# Input.net
KiCad netlist of a schematic drawn in Altium Designer
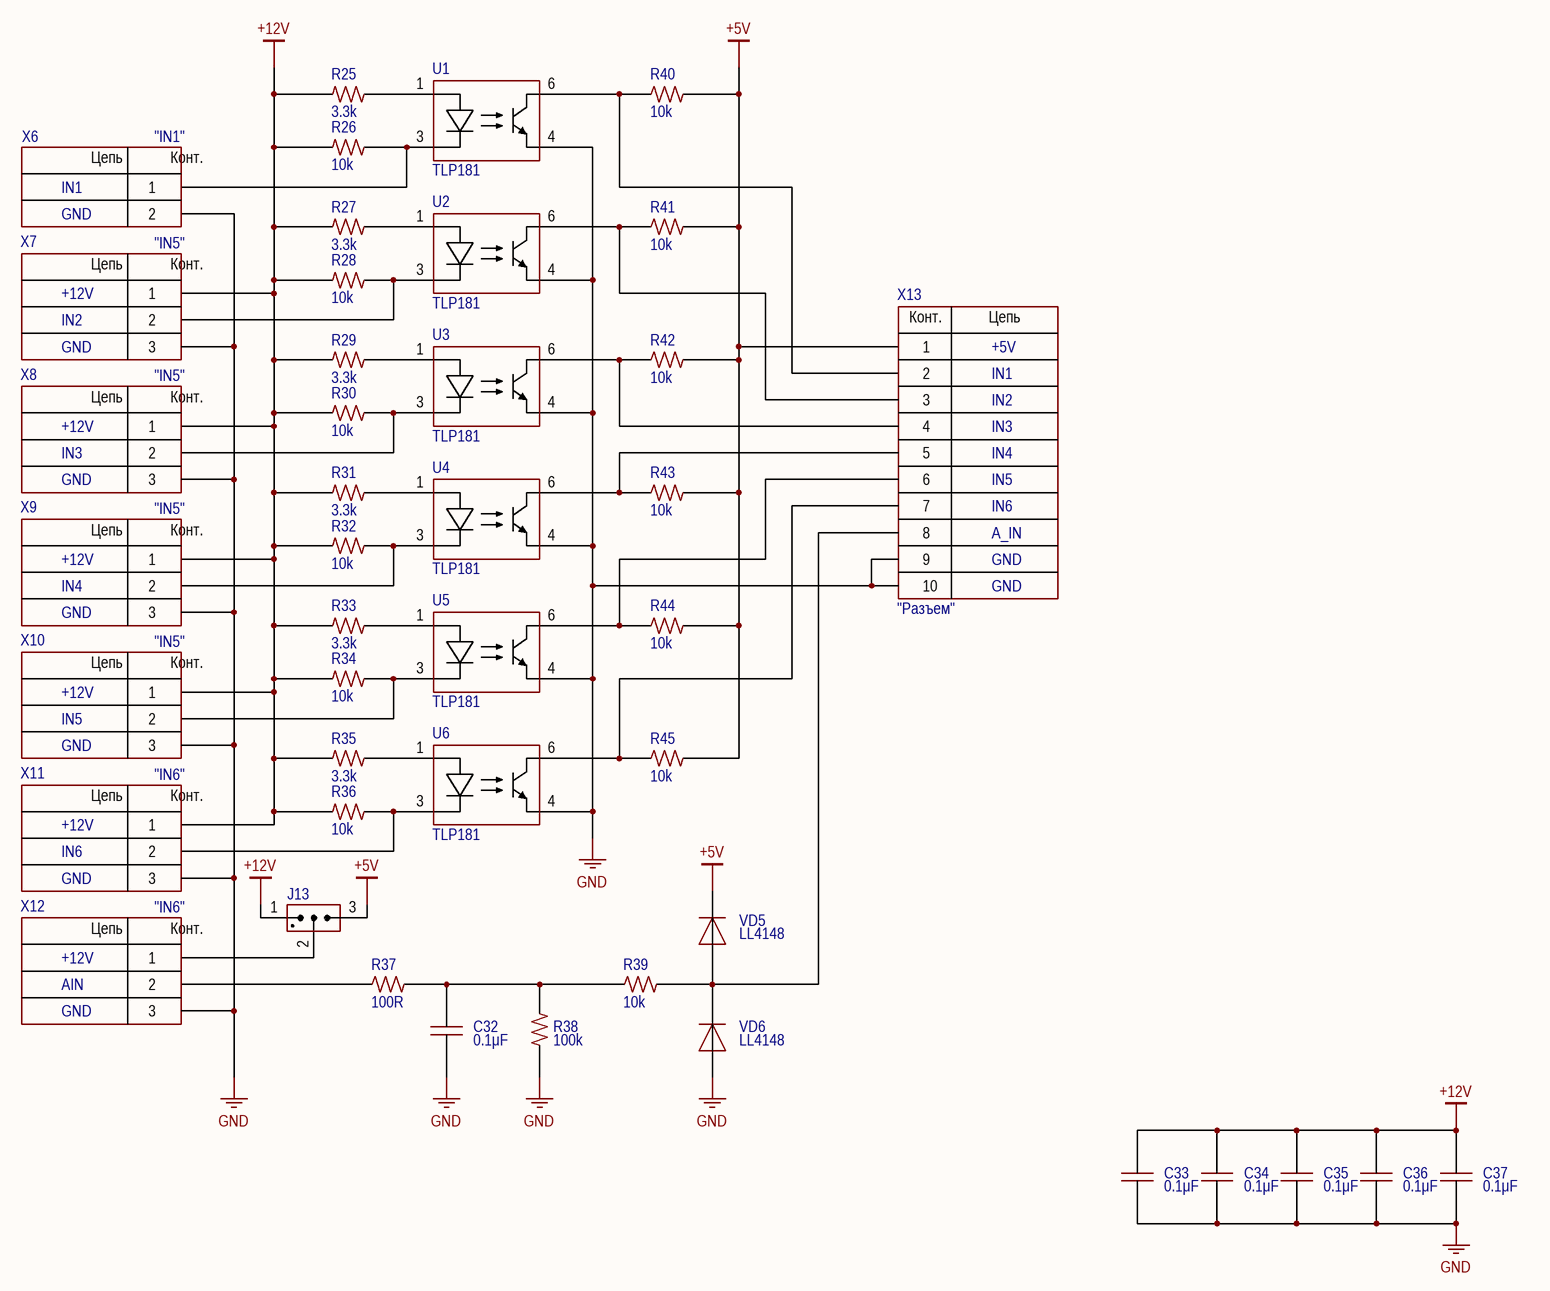
[diagram p0: Input.SchDoc]

(export (version "E")
  (design (tool "Eeschema 10.0.6"))
  (components
    (comp (ref "C32")
      (value "0.1μF")
      (footprint "Standart_Case:CAP: 0805")
      (fields
        (field (name "MANUFACTURER") "Murata Electronics")
        (field (name "PARTNUMBER") "GRM21BR71H104KA01L")
        (field (name "VALUEMANUFACTURERPARTNUMBER") "Керамический конденсатор, 0.1μF, X7R, ±10%, 16V, 0805, -55...+125°C")
      )
      (libsource (lib "Capacitor") (part "Ceramic_0805"))
    )
    (comp (ref "C33")
      (value "0.1μF")
      (footprint "Standart_Case:CAP: 0805")
      (fields
        (field (name "MANUFACTURER") "Murata Electronics")
        (field (name "PARTNUMBER") "GRM21BR71H104KA01L")
        (field (name "VALUEMANUFACTURERPARTNUMBER") "Керамический конденсатор, 0.1μF, X7R, ±10%, 16V, 0805, -55...+125°C")
      )
      (libsource (lib "Capacitor") (part "Ceramic_0805"))
    )
    (comp (ref "C34")
      (value "0.1μF")
      (footprint "Standart_Case:CAP: 0805")
      (fields
        (field (name "MANUFACTURER") "Murata Electronics")
        (field (name "PARTNUMBER") "GRM21BR71H104KA01L")
        (field (name "VALUEMANUFACTURERPARTNUMBER") "Керамический конденсатор, 0.1μF, X7R, ±10%, 16V, 0805, -55...+125°C")
      )
      (libsource (lib "Capacitor") (part "Ceramic_0805"))
    )
    (comp (ref "C35")
      (value "0.1μF")
      (footprint "Standart_Case:CAP: 0805")
      (fields
        (field (name "MANUFACTURER") "Murata Electronics")
        (field (name "PARTNUMBER") "GRM21BR71H104KA01L")
        (field (name "VALUEMANUFACTURERPARTNUMBER") "Керамический конденсатор, 0.1μF, X7R, ±10%, 16V, 0805, -55...+125°C")
      )
      (libsource (lib "Capacitor") (part "Ceramic_0805"))
    )
    (comp (ref "C36")
      (value "0.1μF")
      (footprint "Standart_Case:CAP: 0805")
      (fields
        (field (name "MANUFACTURER") "Murata Electronics")
        (field (name "PARTNUMBER") "GRM21BR71H104KA01L")
        (field (name "VALUEMANUFACTURERPARTNUMBER") "Керамический конденсатор, 0.1μF, X7R, ±10%, 16V, 0805, -55...+125°C")
      )
      (libsource (lib "Capacitor") (part "Ceramic_0805"))
    )
    (comp (ref "C37")
      (value "0.1μF")
      (footprint "Standart_Case:CAP: 0805")
      (fields
        (field (name "MANUFACTURER") "Murata Electronics")
        (field (name "PARTNUMBER") "GRM21BR71H104KA01L")
        (field (name "VALUEMANUFACTURERPARTNUMBER") "Керамический конденсатор, 0.1μF, X7R, ±10%, 16V, 0805, -55...+125°C")
      )
      (libsource (lib "Capacitor") (part "Ceramic_0805"))
    )
    (comp (ref "J13")
      (value "~")
      (footprint "Custom_Case:CON: PLS-3")
      (libsource (lib "Connector") (part "Jumper_3_pin"))
    )
    (comp (ref "R25")
      (value "Резистор SMD")
      (footprint "Standart_Case:RES: 0805")
      (fields (field (name "ЗНАЧЕНИЕ") "3.3k"))
      (libsource (lib "Resistor") (part "Резистор SMD"))
    )
    (comp (ref "R26")
      (value "Резистор SMD")
      (footprint "Standart_Case:RES: 0805")
      (fields (field (name "ЗНАЧЕНИЕ") "10k"))
      (libsource (lib "Resistor") (part "Резистор SMD"))
    )
    (comp (ref "R27")
      (value "Резистор SMD")
      (footprint "Standart_Case:RES: 0805")
      (fields (field (name "ЗНАЧЕНИЕ") "3.3k"))
      (libsource (lib "Resistor") (part "Резистор SMD"))
    )
    (comp (ref "R28")
      (value "Резистор SMD")
      (footprint "Standart_Case:RES: 0805")
      (fields (field (name "ЗНАЧЕНИЕ") "10k"))
      (libsource (lib "Resistor") (part "Резистор SMD"))
    )
    (comp (ref "R29")
      (value "Резистор SMD")
      (footprint "Standart_Case:RES: 0805")
      (fields (field (name "ЗНАЧЕНИЕ") "3.3k"))
      (libsource (lib "Resistor") (part "Резистор SMD"))
    )
    (comp (ref "R30")
      (value "Резистор SMD")
      (footprint "Standart_Case:RES: 0805")
      (fields (field (name "ЗНАЧЕНИЕ") "10k"))
      (libsource (lib "Resistor") (part "Резистор SMD"))
    )
    (comp (ref "R31")
      (value "Резистор SMD")
      (footprint "Standart_Case:RES: 0805")
      (fields (field (name "ЗНАЧЕНИЕ") "3.3k"))
      (libsource (lib "Resistor") (part "Резистор SMD"))
    )
    (comp (ref "R32")
      (value "Резистор SMD")
      (footprint "Standart_Case:RES: 0805")
      (fields (field (name "ЗНАЧЕНИЕ") "10k"))
      (libsource (lib "Resistor") (part "Резистор SMD"))
    )
    (comp (ref "R33")
      (value "Резистор SMD")
      (footprint "Standart_Case:RES: 0805")
      (fields (field (name "ЗНАЧЕНИЕ") "3.3k"))
      (libsource (lib "Resistor") (part "Резистор SMD"))
    )
    (comp (ref "R34")
      (value "Резистор SMD")
      (footprint "Standart_Case:RES: 0805")
      (fields (field (name "ЗНАЧЕНИЕ") "10k"))
      (libsource (lib "Resistor") (part "Резистор SMD"))
    )
    (comp (ref "R35")
      (value "Резистор SMD")
      (footprint "Standart_Case:RES: 0805")
      (fields (field (name "ЗНАЧЕНИЕ") "3.3k"))
      (libsource (lib "Resistor") (part "Резистор SMD"))
    )
    (comp (ref "R36")
      (value "Резистор SMD")
      (footprint "Standart_Case:RES: 0805")
      (fields (field (name "ЗНАЧЕНИЕ") "10k"))
      (libsource (lib "Resistor") (part "Резистор SMD"))
    )
    (comp (ref "R37")
      (value "Резистор SMD")
      (footprint "Standart_Case:RES: 0805")
      (fields (field (name "ЗНАЧЕНИЕ") "100R"))
      (libsource (lib "Resistor") (part "Резистор SMD"))
    )
    (comp (ref "R38")
      (value "Резистор SMD")
      (footprint "Standart_Case:RES: 0805")
      (fields (field (name "ЗНАЧЕНИЕ") "100k"))
      (libsource (lib "Resistor") (part "Резистор SMD"))
    )
    (comp (ref "R39")
      (value "Резистор SMD")
      (footprint "Standart_Case:RES: 0805")
      (fields (field (name "ЗНАЧЕНИЕ") "10k"))
      (libsource (lib "Resistor") (part "Резистор SMD"))
    )
    (comp (ref "R40")
      (value "Резистор SMD")
      (footprint "Standart_Case:RES: 0805")
      (fields (field (name "ЗНАЧЕНИЕ") "10k"))
      (libsource (lib "Resistor") (part "Резистор SMD"))
    )
    (comp (ref "R41")
      (value "Резистор SMD")
      (footprint "Standart_Case:RES: 0805")
      (fields (field (name "ЗНАЧЕНИЕ") "10k"))
      (libsource (lib "Resistor") (part "Резистор SMD"))
    )
    (comp (ref "R42")
      (value "Резистор SMD")
      (footprint "Standart_Case:RES: 0805")
      (fields (field (name "ЗНАЧЕНИЕ") "10k"))
      (libsource (lib "Resistor") (part "Резистор SMD"))
    )
    (comp (ref "R43")
      (value "Резистор SMD")
      (footprint "Standart_Case:RES: 0805")
      (fields (field (name "ЗНАЧЕНИЕ") "10k"))
      (libsource (lib "Resistor") (part "Резистор SMD"))
    )
    (comp (ref "R44")
      (value "Резистор SMD")
      (footprint "Standart_Case:RES: 0805")
      (fields (field (name "ЗНАЧЕНИЕ") "10k"))
      (libsource (lib "Resistor") (part "Резистор SMD"))
    )
    (comp (ref "R45")
      (value "Резистор SMD")
      (footprint "Standart_Case:RES: 0805")
      (fields (field (name "ЗНАЧЕНИЕ") "10k"))
      (libsource (lib "Resistor") (part "Резистор SMD"))
    )
    (comp (ref "U1")
      (value "~")
      (footprint "Custom_Case:OPTO: TLP181")
      (description "Optoisolator")
      (fields (field (name "MANUFACTURER") "Toshiba") (field (name "PARTNUMBER") "TLP181"))
      (libsource (lib "Optoisolator") (part "TLP181"))
    )
    (comp (ref "U2")
      (value "~")
      (footprint "Custom_Case:OPTO: TLP181")
      (description "Optoisolator")
      (fields (field (name "MANUFACTURER") "Toshiba") (field (name "PARTNUMBER") "TLP181"))
      (libsource (lib "Optoisolator") (part "TLP181"))
    )
    (comp (ref "U3")
      (value "~")
      (footprint "Custom_Case:OPTO: TLP181")
      (description "Optoisolator")
      (fields (field (name "MANUFACTURER") "Toshiba") (field (name "PARTNUMBER") "TLP181"))
      (libsource (lib "Optoisolator") (part "TLP181"))
    )
    (comp (ref "U4")
      (value "~")
      (footprint "Custom_Case:OPTO: TLP181")
      (description "Optoisolator")
      (fields (field (name "MANUFACTURER") "Toshiba") (field (name "PARTNUMBER") "TLP181"))
      (libsource (lib "Optoisolator") (part "TLP181"))
    )
    (comp (ref "U5")
      (value "~")
      (footprint "Custom_Case:OPTO: TLP181")
      (description "Optoisolator")
      (fields (field (name "MANUFACTURER") "Toshiba") (field (name "PARTNUMBER") "TLP181"))
      (libsource (lib "Optoisolator") (part "TLP181"))
    )
    (comp (ref "U6")
      (value "~")
      (footprint "Custom_Case:OPTO: TLP181")
      (description "Optoisolator")
      (fields (field (name "MANUFACTURER") "Toshiba") (field (name "PARTNUMBER") "TLP181"))
      (libsource (lib "Optoisolator") (part "TLP181"))
    )
    (comp (ref "VD5")
      (value "~")
      (footprint "Standart_Case:DIODE: SOD80")
      (fields
        (field (name "MANUFACTURER") "Micro Commercial")
        (field (name "VALUEMANUFACTURERPARTNUMBER") "Single diode, 75V, 150mA, 1V, 4ns, SOD-323, -55...+150°C")
        (field (name "VOLTAGE") "75V")
        (field (name "PARTNUMBER") "LL4148")
      )
      (libsource (lib "Diode") (part "Diode_single"))
    )
    (comp (ref "VD6")
      (value "~")
      (footprint "Standart_Case:DIODE: SOD80")
      (fields
        (field (name "MANUFACTURER") "Micro Commercial")
        (field (name "VALUEMANUFACTURERPARTNUMBER") "Single diode, 75V, 150mA, 1V, 4ns, SOD-323, -55...+150°C")
        (field (name "VOLTAGE") "75V")
        (field (name "PARTNUMBER") "LL4148")
      )
      (libsource (lib "Diode") (part "Diode_single"))
    )
    (comp (ref "X6")
      (value "~")
      (footprint "Custom_Case:CON: 15EDGVC-3.5-02 (or 691321100002)")
      (fields
        (field (name "MANUFACTURER") "DEGSON")
        (field (name "VALUEMANUFACTURERPARTNUMBER") "Клеммник, 2pin, 3.5mm, 300VAC, 10A")
        (field (name "PARTNUMBER") "DG350-3.5-02P-14-00A(H)")
        (field (name "COMMENTTEXT") "\"IN1\"")
      )
      (libsource (lib "Connector") (part "Connector_terminal_2pin"))
    )
    (comp (ref "X7")
      (value "~")
      (footprint "Custom_Case:CON: 15EDGVC-3.5-03 (or 691321100003)")
      (fields
        (field (name "MANUFACTURER") "Degson")
        (field (name "VALUEMANUFACTURERPARTNUMBER") "Terminal connector, 3pin, 3.5mm, 300VAC, 10A")
        (field (name "PARTNUMBER") "DG350-3.5-03P-14")
        (field (name "COMMENTTEXT") "\"IN5\"")
      )
      (libsource (lib "Connector") (part "Connector_terminal_3pin"))
    )
    (comp (ref "X8")
      (value "~")
      (footprint "Custom_Case:CON: 15EDGVC-3.5-03 (or 691321100003)")
      (fields
        (field (name "MANUFACTURER") "Degson")
        (field (name "VALUEMANUFACTURERPARTNUMBER") "Terminal connector, 3pin, 3.5mm, 300VAC, 10A")
        (field (name "PARTNUMBER") "DG350-3.5-03P-14")
        (field (name "COMMENTTEXT") "\"IN5\"")
      )
      (libsource (lib "Connector") (part "Connector_terminal_3pin"))
    )
    (comp (ref "X9")
      (value "~")
      (footprint "Custom_Case:CON: 15EDGVC-3.5-03 (or 691321100003)")
      (fields
        (field (name "MANUFACTURER") "Degson")
        (field (name "VALUEMANUFACTURERPARTNUMBER") "Terminal connector, 3pin, 3.5mm, 300VAC, 10A")
        (field (name "PARTNUMBER") "DG350-3.5-03P-14")
        (field (name "COMMENTTEXT") "\"IN5\"")
      )
      (libsource (lib "Connector") (part "Connector_terminal_3pin"))
    )
    (comp (ref "X10")
      (value "~")
      (footprint "Custom_Case:CON: 15EDGVC-3.5-03 (or 691321100003)")
      (fields
        (field (name "MANUFACTURER") "Degson")
        (field (name "VALUEMANUFACTURERPARTNUMBER") "Terminal connector, 3pin, 3.5mm, 300VAC, 10A")
        (field (name "PARTNUMBER") "DG350-3.5-03P-14")
        (field (name "COMMENTTEXT") "\"IN5\"")
      )
      (libsource (lib "Connector") (part "Connector_terminal_3pin"))
    )
    (comp (ref "X11")
      (value "~")
      (footprint "Custom_Case:CON: 15EDGVC-3.5-03 (or 691321100003)")
      (fields
        (field (name "MANUFACTURER") "Degson")
        (field (name "VALUEMANUFACTURERPARTNUMBER") "Terminal connector, 3pin, 3.5mm, 300VAC, 10A")
        (field (name "PARTNUMBER") "DG350-3.5-03P-14")
        (field (name "COMMENTTEXT") "\"IN6\"")
      )
      (libsource (lib "Connector") (part "Connector_terminal_3pin"))
    )
    (comp (ref "X12")
      (value "~")
      (footprint "Custom_Case:CON: 15EDGVC-3.5-03 (or 691321100003)")
      (fields
        (field (name "MANUFACTURER") "Degson")
        (field (name "VALUEMANUFACTURERPARTNUMBER") "Terminal connector, 3pin, 3.5mm, 300VAC, 10A")
        (field (name "PARTNUMBER") "DG350-3.5-03P-14")
        (field (name "COMMENTTEXT") "\"IN6\"")
      )
      (libsource (lib "Connector") (part "Connector_terminal_3pin"))
    )
    (comp (ref "X13")
      (value "~")
      (footprint "Custom_Case:CON: PLS-10")
      (fields
        (field (name "MANUFACTURER") "Connfly")
        (field (name "VALUEMANUFACTURERPARTNUMBER") "Connector, 10pin, 2.54mm, 500VAC, 3A")
        (field (name "PARTNUMBER") "PLS-10")
        (field (name "COMMENTTEXT") "\"Разъем\"")
      )
      (libsource (lib "Connector") (part "PLS-10"))
    )
  )
  (nets
    (net (code "1") (name "+5V") (class "Default")
      (node (ref "J13") (pin "3") (pinfunction "IN_3") (pintype "passive"))
      (node (ref "R40") (pin "2") (pinfunction "2_2") (pintype "passive"))
      (node (ref "R41") (pin "2") (pinfunction "2_2") (pintype "passive"))
      (node (ref "R42") (pin "2") (pinfunction "2_2") (pintype "passive"))
      (node (ref "R43") (pin "2") (pinfunction "2_2") (pintype "passive"))
      (node (ref "R44") (pin "2") (pinfunction "2_2") (pintype "passive"))
      (node (ref "R45") (pin "2") (pinfunction "2_2") (pintype "passive"))
      (node (ref "VD5") (pin "2") (pinfunction "2_2") (pintype "passive"))
      (node (ref "X13") (pin "1") (pinfunction "1_1") (pintype "passive"))
    )
    (net (code "2") (name "+12V") (class "Default")
      (node (ref "C33") (pin "2") (pinfunction "2_2") (pintype "passive"))
      (node (ref "C34") (pin "2") (pinfunction "2_2") (pintype "passive"))
      (node (ref "C35") (pin "2") (pinfunction "2_2") (pintype "passive"))
      (node (ref "C36") (pin "2") (pinfunction "2_2") (pintype "passive"))
      (node (ref "C37") (pin "2") (pinfunction "2_2") (pintype "passive"))
      (node (ref "J13") (pin "1") (pinfunction "IN_1") (pintype "passive"))
      (node (ref "R25") (pin "1") (pinfunction "1_1") (pintype "passive"))
      (node (ref "R26") (pin "1") (pinfunction "1_1") (pintype "passive"))
      (node (ref "R27") (pin "1") (pinfunction "1_1") (pintype "passive"))
      (node (ref "R28") (pin "1") (pinfunction "1_1") (pintype "passive"))
      (node (ref "R29") (pin "1") (pinfunction "1_1") (pintype "passive"))
      (node (ref "R30") (pin "1") (pinfunction "1_1") (pintype "passive"))
      (node (ref "R31") (pin "1") (pinfunction "1_1") (pintype "passive"))
      (node (ref "R32") (pin "1") (pinfunction "1_1") (pintype "passive"))
      (node (ref "R33") (pin "1") (pinfunction "1_1") (pintype "passive"))
      (node (ref "R34") (pin "1") (pinfunction "1_1") (pintype "passive"))
      (node (ref "R35") (pin "1") (pinfunction "1_1") (pintype "passive"))
      (node (ref "R36") (pin "1") (pinfunction "1_1") (pintype "passive"))
      (node (ref "X10") (pin "1") (pinfunction "1_1") (pintype "passive"))
      (node (ref "X11") (pin "1") (pinfunction "1_1") (pintype "passive"))
      (node (ref "X7") (pin "1") (pinfunction "1_1") (pintype "passive"))
      (node (ref "X8") (pin "1") (pinfunction "1_1") (pintype "passive"))
      (node (ref "X9") (pin "1") (pinfunction "1_1") (pintype "passive"))
    )
    (net (code "3") (name "GND") (class "Default")
      (node (ref "C32") (pin "1") (pinfunction "1_1") (pintype "passive"))
      (node (ref "C33") (pin "1") (pinfunction "1_1") (pintype "passive"))
      (node (ref "C34") (pin "1") (pinfunction "1_1") (pintype "passive"))
      (node (ref "C35") (pin "1") (pinfunction "1_1") (pintype "passive"))
      (node (ref "C36") (pin "1") (pinfunction "1_1") (pintype "passive"))
      (node (ref "C37") (pin "1") (pinfunction "1_1") (pintype "passive"))
      (node (ref "R38") (pin "1") (pinfunction "1_1") (pintype "passive"))
      (node (ref "U1") (pin "4") (pinfunction "E_4") (pintype "passive"))
      (node (ref "U2") (pin "4") (pinfunction "E_4") (pintype "passive"))
      (node (ref "U3") (pin "4") (pinfunction "E_4") (pintype "passive"))
      (node (ref "U4") (pin "4") (pinfunction "E_4") (pintype "passive"))
      (node (ref "U5") (pin "4") (pinfunction "E_4") (pintype "passive"))
      (node (ref "U6") (pin "4") (pinfunction "E_4") (pintype "passive"))
      (node (ref "VD6") (pin "1") (pinfunction "1_1") (pintype "passive"))
      (node (ref "X10") (pin "3") (pinfunction "3_3") (pintype "power_in"))
      (node (ref "X11") (pin "3") (pinfunction "3_3") (pintype "power_in"))
      (node (ref "X12") (pin "3") (pinfunction "3_3") (pintype "power_in"))
      (node (ref "X13") (pin "10") (pinfunction "10_10") (pintype "power_in"))
      (node (ref "X13") (pin "9") (pinfunction "9_9") (pintype "power_in"))
      (node (ref "X6") (pin "2") (pinfunction "2_2") (pintype "passive"))
      (node (ref "X7") (pin "3") (pinfunction "3_3") (pintype "power_in"))
      (node (ref "X8") (pin "3") (pinfunction "3_3") (pintype "power_in"))
      (node (ref "X9") (pin "3") (pinfunction "3_3") (pintype "power_in"))
    )
    (net (code "4") (name "Net-(C32-Pad2)") (class "Default")
      (node (ref "C32") (pin "2") (pinfunction "2_2") (pintype "passive"))
      (node (ref "R37") (pin "2") (pinfunction "2_2") (pintype "passive"))
      (node (ref "R38") (pin "2") (pinfunction "2_2") (pintype "passive"))
      (node (ref "R39") (pin "1") (pinfunction "1_1") (pintype "passive"))
    )
    (net (code "5") (name "Net-(J13-IN-Pad2)") (class "Default")
      (node (ref "J13") (pin "2") (pinfunction "IN_2") (pintype "passive"))
      (node (ref "X12") (pin "1") (pinfunction "1_1") (pintype "passive"))
    )
    (net (code "6") (name "Net-(R26-Pad2)") (class "Default")
      (node (ref "R26") (pin "2") (pinfunction "2_2") (pintype "passive"))
      (node (ref "U1") (pin "3") (pinfunction "C_3") (pintype "passive"))
      (node (ref "X6") (pin "1") (pinfunction "1_1") (pintype "passive"))
    )
    (net (code "7") (name "Net-(R28-Pad2)") (class "Default")
      (node (ref "R28") (pin "2") (pinfunction "2_2") (pintype "passive"))
      (node (ref "U2") (pin "3") (pinfunction "C_3") (pintype "passive"))
      (node (ref "X7") (pin "2") (pinfunction "2_2") (pintype "passive"))
    )
    (net (code "8") (name "Net-(R30-Pad2)") (class "Default")
      (node (ref "R30") (pin "2") (pinfunction "2_2") (pintype "passive"))
      (node (ref "U3") (pin "3") (pinfunction "C_3") (pintype "passive"))
      (node (ref "X8") (pin "2") (pinfunction "2_2") (pintype "passive"))
    )
    (net (code "9") (name "Net-(R32-Pad2)") (class "Default")
      (node (ref "R32") (pin "2") (pinfunction "2_2") (pintype "passive"))
      (node (ref "U4") (pin "3") (pinfunction "C_3") (pintype "passive"))
      (node (ref "X9") (pin "2") (pinfunction "2_2") (pintype "passive"))
    )
    (net (code "10") (name "Net-(R34-Pad2)") (class "Default")
      (node (ref "R34") (pin "2") (pinfunction "2_2") (pintype "passive"))
      (node (ref "U5") (pin "3") (pinfunction "C_3") (pintype "passive"))
      (node (ref "X10") (pin "2") (pinfunction "2_2") (pintype "passive"))
    )
    (net (code "11") (name "Net-(R36-Pad2)") (class "Default")
      (node (ref "R36") (pin "2") (pinfunction "2_2") (pintype "passive"))
      (node (ref "U6") (pin "3") (pinfunction "C_3") (pintype "passive"))
      (node (ref "X11") (pin "2") (pinfunction "2_2") (pintype "passive"))
    )
    (net (code "12") (name "Net-(R37-Pad1)") (class "Default")
      (node (ref "R37") (pin "1") (pinfunction "1_1") (pintype "passive"))
      (node (ref "X12") (pin "2") (pinfunction "2_2") (pintype "passive"))
    )
    (net (code "13") (name "Net-(R39-Pad2)") (class "Default")
      (node (ref "R39") (pin "2") (pinfunction "2_2") (pintype "passive"))
      (node (ref "VD5") (pin "1") (pinfunction "1_1") (pintype "passive"))
      (node (ref "VD6") (pin "2") (pinfunction "2_2") (pintype "passive"))
      (node (ref "X13") (pin "8") (pinfunction "8_8") (pintype "power_in"))
    )
    (net (code "14") (name "Net-(R40-Pad1)") (class "Default")
      (node (ref "R40") (pin "1") (pinfunction "1_1") (pintype "passive"))
      (node (ref "U1") (pin "6") (pinfunction "C_6") (pintype "passive"))
      (node (ref "X13") (pin "2") (pinfunction "2_2") (pintype "passive"))
    )
    (net (code "15") (name "Net-(R41-Pad1)") (class "Default")
      (node (ref "R41") (pin "1") (pinfunction "1_1") (pintype "passive"))
      (node (ref "U2") (pin "6") (pinfunction "C_6") (pintype "passive"))
      (node (ref "X13") (pin "3") (pinfunction "3_3") (pintype "power_in"))
    )
    (net (code "16") (name "Net-(R42-Pad1)") (class "Default")
      (node (ref "R42") (pin "1") (pinfunction "1_1") (pintype "passive"))
      (node (ref "U3") (pin "6") (pinfunction "C_6") (pintype "passive"))
      (node (ref "X13") (pin "4") (pinfunction "4_4") (pintype "power_in"))
    )
    (net (code "17") (name "Net-(R43-Pad1)") (class "Default")
      (node (ref "R43") (pin "1") (pinfunction "1_1") (pintype "passive"))
      (node (ref "U4") (pin "6") (pinfunction "C_6") (pintype "passive"))
      (node (ref "X13") (pin "5") (pinfunction "5_5") (pintype "power_in"))
    )
    (net (code "18") (name "Net-(R44-Pad1)") (class "Default")
      (node (ref "R44") (pin "1") (pinfunction "1_1") (pintype "passive"))
      (node (ref "U5") (pin "6") (pinfunction "C_6") (pintype "passive"))
      (node (ref "X13") (pin "6") (pinfunction "6_6") (pintype "power_in"))
    )
    (net (code "19") (name "Net-(R45-Pad1)") (class "Default")
      (node (ref "R45") (pin "1") (pinfunction "1_1") (pintype "passive"))
      (node (ref "U6") (pin "6") (pinfunction "C_6") (pintype "passive"))
      (node (ref "X13") (pin "7") (pinfunction "7_7") (pintype "power_in"))
    )
    (net (code "20") (name "Net-(U1-A)") (class "Default")
      (node (ref "R25") (pin "2") (pinfunction "2_2") (pintype "passive"))
      (node (ref "U1") (pin "1") (pinfunction "A_1") (pintype "passive"))
    )
    (net (code "21") (name "Net-(U2-A)") (class "Default")
      (node (ref "R27") (pin "2") (pinfunction "2_2") (pintype "passive"))
      (node (ref "U2") (pin "1") (pinfunction "A_1") (pintype "passive"))
    )
    (net (code "22") (name "Net-(U3-A)") (class "Default")
      (node (ref "R29") (pin "2") (pinfunction "2_2") (pintype "passive"))
      (node (ref "U3") (pin "1") (pinfunction "A_1") (pintype "passive"))
    )
    (net (code "23") (name "Net-(U4-A)") (class "Default")
      (node (ref "R31") (pin "2") (pinfunction "2_2") (pintype "passive"))
      (node (ref "U4") (pin "1") (pinfunction "A_1") (pintype "passive"))
    )
    (net (code "24") (name "Net-(U5-A)") (class "Default")
      (node (ref "R33") (pin "2") (pinfunction "2_2") (pintype "passive"))
      (node (ref "U5") (pin "1") (pinfunction "A_1") (pintype "passive"))
    )
    (net (code "25") (name "Net-(U6-A)") (class "Default")
      (node (ref "R35") (pin "2") (pinfunction "2_2") (pintype "passive"))
      (node (ref "U6") (pin "1") (pinfunction "A_1") (pintype "passive"))
    )
  )
)
